# Hall_sensor_cable.net
KiCad netlist of a schematic drawn in Altium Designer
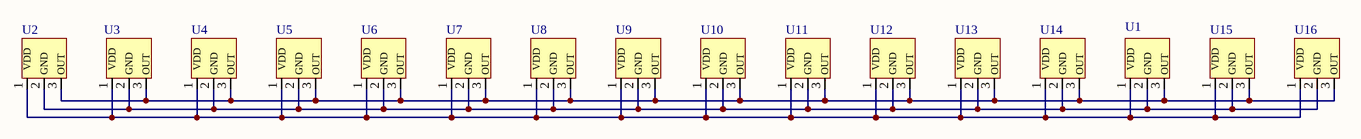
[diagram p0: Hall sensor cable.SchDoc]

(export (version "E")
  (design (tool "Eeschema 10.0.6"))
  (components
    (comp (ref "U1")
      (value "U1881_Hall")
      (footprint "U1881")
      (libsource (lib "Integrated_Circuts") (part "U1881_Hall"))
    )
    (comp (ref "U2")
      (value "U1881_Hall")
      (footprint "U1881")
      (libsource (lib "Integrated_Circuts") (part "U1881_Hall"))
    )
    (comp (ref "U3")
      (value "U1881_Hall")
      (footprint "U1881")
      (libsource (lib "Integrated_Circuts") (part "U1881_Hall"))
    )
    (comp (ref "U4")
      (value "U1881_Hall")
      (footprint "U1881")
      (libsource (lib "Integrated_Circuts") (part "U1881_Hall"))
    )
    (comp (ref "U5")
      (value "U1881_Hall")
      (footprint "U1881")
      (libsource (lib "Integrated_Circuts") (part "U1881_Hall"))
    )
    (comp (ref "U6")
      (value "U1881_Hall")
      (footprint "U1881")
      (libsource (lib "Integrated_Circuts") (part "U1881_Hall"))
    )
    (comp (ref "U7")
      (value "U1881_Hall")
      (footprint "U1881")
      (libsource (lib "Integrated_Circuts") (part "U1881_Hall"))
    )
    (comp (ref "U8")
      (value "U1881_Hall")
      (footprint "U1881")
      (libsource (lib "Integrated_Circuts") (part "U1881_Hall"))
    )
    (comp (ref "U9")
      (value "U1881_Hall")
      (footprint "U1881")
      (libsource (lib "Integrated_Circuts") (part "U1881_Hall"))
    )
    (comp (ref "U10")
      (value "U1881_Hall")
      (footprint "U1881")
      (libsource (lib "Integrated_Circuts") (part "U1881_Hall"))
    )
    (comp (ref "U11")
      (value "U1881_Hall")
      (footprint "U1881")
      (libsource (lib "Integrated_Circuts") (part "U1881_Hall"))
    )
    (comp (ref "U12")
      (value "U1881_Hall")
      (footprint "U1881")
      (libsource (lib "Integrated_Circuts") (part "U1881_Hall"))
    )
    (comp (ref "U13")
      (value "U1881_Hall")
      (footprint "U1881")
      (libsource (lib "Integrated_Circuts") (part "U1881_Hall"))
    )
    (comp (ref "U14")
      (value "U1881_Hall")
      (footprint "U1881")
      (libsource (lib "Integrated_Circuts") (part "U1881_Hall"))
    )
    (comp (ref "U15")
      (value "U1881_Hall")
      (footprint "U1881")
      (libsource (lib "Integrated_Circuts") (part "U1881_Hall"))
    )
    (comp (ref "U16")
      (value "U1881_Hall")
      (footprint "U1881")
      (libsource (lib "Integrated_Circuts") (part "U1881_Hall"))
    )
  )
  (nets
    (net (code "1") (name "Net-(U1-GND)") (class "Default")
      (node (ref "U1") (pin "2") (pinfunction "GND_2") (pintype "passive"))
      (node (ref "U10") (pin "2") (pinfunction "GND_2") (pintype "passive"))
      (node (ref "U11") (pin "2") (pinfunction "GND_2") (pintype "passive"))
      (node (ref "U12") (pin "2") (pinfunction "GND_2") (pintype "passive"))
      (node (ref "U13") (pin "2") (pinfunction "GND_2") (pintype "passive"))
      (node (ref "U14") (pin "2") (pinfunction "GND_2") (pintype "passive"))
      (node (ref "U15") (pin "2") (pinfunction "GND_2") (pintype "passive"))
      (node (ref "U16") (pin "2") (pinfunction "GND_2") (pintype "passive"))
      (node (ref "U2") (pin "2") (pinfunction "GND_2") (pintype "passive"))
      (node (ref "U3") (pin "2") (pinfunction "GND_2") (pintype "passive"))
      (node (ref "U4") (pin "2") (pinfunction "GND_2") (pintype "passive"))
      (node (ref "U5") (pin "2") (pinfunction "GND_2") (pintype "passive"))
      (node (ref "U6") (pin "2") (pinfunction "GND_2") (pintype "passive"))
      (node (ref "U7") (pin "2") (pinfunction "GND_2") (pintype "passive"))
      (node (ref "U8") (pin "2") (pinfunction "GND_2") (pintype "passive"))
      (node (ref "U9") (pin "2") (pinfunction "GND_2") (pintype "passive"))
    )
    (net (code "2") (name "Net-(U1-OUT)") (class "Default")
      (node (ref "U1") (pin "3") (pinfunction "OUT_3") (pintype "passive"))
      (node (ref "U10") (pin "3") (pinfunction "OUT_3") (pintype "passive"))
      (node (ref "U11") (pin "3") (pinfunction "OUT_3") (pintype "passive"))
      (node (ref "U12") (pin "3") (pinfunction "OUT_3") (pintype "passive"))
      (node (ref "U13") (pin "3") (pinfunction "OUT_3") (pintype "passive"))
      (node (ref "U14") (pin "3") (pinfunction "OUT_3") (pintype "passive"))
      (node (ref "U15") (pin "3") (pinfunction "OUT_3") (pintype "passive"))
      (node (ref "U16") (pin "3") (pinfunction "OUT_3") (pintype "passive"))
      (node (ref "U2") (pin "3") (pinfunction "OUT_3") (pintype "passive"))
      (node (ref "U3") (pin "3") (pinfunction "OUT_3") (pintype "passive"))
      (node (ref "U4") (pin "3") (pinfunction "OUT_3") (pintype "passive"))
      (node (ref "U5") (pin "3") (pinfunction "OUT_3") (pintype "passive"))
      (node (ref "U6") (pin "3") (pinfunction "OUT_3") (pintype "passive"))
      (node (ref "U7") (pin "3") (pinfunction "OUT_3") (pintype "passive"))
      (node (ref "U8") (pin "3") (pinfunction "OUT_3") (pintype "passive"))
      (node (ref "U9") (pin "3") (pinfunction "OUT_3") (pintype "passive"))
    )
    (net (code "3") (name "Net-(U1-VDD)") (class "Default")
      (node (ref "U1") (pin "1") (pinfunction "VDD_1") (pintype "passive"))
      (node (ref "U10") (pin "1") (pinfunction "VDD_1") (pintype "passive"))
      (node (ref "U11") (pin "1") (pinfunction "VDD_1") (pintype "passive"))
      (node (ref "U12") (pin "1") (pinfunction "VDD_1") (pintype "passive"))
      (node (ref "U13") (pin "1") (pinfunction "VDD_1") (pintype "passive"))
      (node (ref "U14") (pin "1") (pinfunction "VDD_1") (pintype "passive"))
      (node (ref "U15") (pin "1") (pinfunction "VDD_1") (pintype "passive"))
      (node (ref "U16") (pin "1") (pinfunction "VDD_1") (pintype "passive"))
      (node (ref "U2") (pin "1") (pinfunction "VDD_1") (pintype "passive"))
      (node (ref "U3") (pin "1") (pinfunction "VDD_1") (pintype "passive"))
      (node (ref "U4") (pin "1") (pinfunction "VDD_1") (pintype "passive"))
      (node (ref "U5") (pin "1") (pinfunction "VDD_1") (pintype "passive"))
      (node (ref "U6") (pin "1") (pinfunction "VDD_1") (pintype "passive"))
      (node (ref "U7") (pin "1") (pinfunction "VDD_1") (pintype "passive"))
      (node (ref "U8") (pin "1") (pinfunction "VDD_1") (pintype "passive"))
      (node (ref "U9") (pin "1") (pinfunction "VDD_1") (pintype "passive"))
    )
  )
)
